# NUCLEO-F410RB-Show.net
KiCad netlist of a schematic drawn in Altium Designer
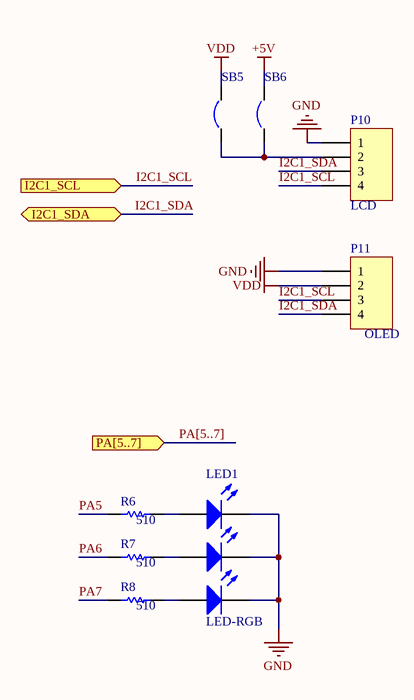
[diagram p0: NUCLEO-F410RB-Show.SchDoc]

(export (version "E")
  (design (tool "Eeschema 10.0.6"))
  (components
    (comp (ref "LED1")
      (value "LED-RGB")
      (footprint "LED-SMD_6PIN-L1.60-W1.50-BL-RD")
      (description "Typical INFRARED GaAs LED")
      (fields (field (name "PUBLISHER") "Altium Limited"))
      (libsource (lib "baselib") (part "LED-RGB"))
    )
    (comp (ref "P10")
      (value "LCD")
      (footprint "HDR1X4")
      (description "Header, 4-Pin")
      (fields (field (name "PUBLISHER") "Altium Limited"))
      (libsource (lib "Connectors") (part "Header 4"))
    )
    (comp (ref "P11")
      (value "OLED")
      (footprint "HDR1X4")
      (description "Header, 4-Pin")
      (fields (field (name "PUBLISHER") "Altium Limited"))
      (libsource (lib "Connectors") (part "Header 4"))
    )
    (comp (ref "R6")
      (value "510")
      (footprint "R0603")
      (description "Resistor")
      (fields (field (name "Comment") "Res_US") (field (name "PUBLISHER") "Altium Limited"))
      (libsource (lib "baselib") (part "Res_US"))
    )
    (comp (ref "R7")
      (value "510")
      (footprint "R0603")
      (description "Resistor")
      (fields (field (name "Comment") "Res_US") (field (name "PUBLISHER") "Altium Limited"))
      (libsource (lib "baselib") (part "Res_US"))
    )
    (comp (ref "R8")
      (value "510")
      (footprint "R0603")
      (description "Resistor")
      (fields (field (name "Comment") "Res_US") (field (name "PUBLISHER") "Altium Limited"))
      (libsource (lib "baselib") (part "Res_US"))
    )
    (comp (ref "SB5")
      (value "Circuit Breaker")
      (footprint "JP2_SMD")
      (fields (field (name "PUBLISHER") "Altium Limited"))
      (libsource (lib "baselib") (part "Circuit Breaker"))
    )
    (comp (ref "SB6")
      (value "Circuit Breaker")
      (footprint "JP2_SMD")
      (fields (field (name "PUBLISHER") "Altium Limited"))
      (libsource (lib "baselib") (part "Circuit Breaker"))
    )
  )
  (nets
    (net (code "1") (name "+5V") (class "Default")
      (node (ref "SB6") (pin "2") (pinfunction "2_2") (pintype "passive"))
    )
    (net (code "2") (name "/I2C1_SCL") (class "Default")
      (node (ref "P10") (pin "4") (pinfunction "4_4") (pintype "passive"))
      (node (ref "P11") (pin "3") (pinfunction "3_3") (pintype "passive"))
    )
    (net (code "3") (name "/I2C1_SDA") (class "Default")
      (node (ref "P10") (pin "3") (pinfunction "3_3") (pintype "passive"))
      (node (ref "P11") (pin "4") (pinfunction "4_4") (pintype "passive"))
    )
    (net (code "4") (name "/PA5") (class "Default")
      (node (ref "R6") (pin "2") (pinfunction "2_2") (pintype "passive"))
    )
    (net (code "5") (name "/PA6") (class "Default")
      (node (ref "R7") (pin "2") (pinfunction "2_2") (pintype "passive"))
    )
    (net (code "6") (name "/PA7") (class "Default")
      (node (ref "R8") (pin "2") (pinfunction "2_2") (pintype "passive"))
    )
    (net (code "8") (name "GND") (class "Default")
      (node (ref "LED1") (pin "4") (pinfunction "K_4") (pintype "passive"))
      (node (ref "LED1") (pin "5") (pinfunction "K_5") (pintype "passive"))
      (node (ref "LED1") (pin "6") (pinfunction "K_6") (pintype "passive"))
      (node (ref "P10") (pin "1") (pinfunction "1_1") (pintype "passive"))
      (node (ref "P11") (pin "1") (pinfunction "1_1") (pintype "passive"))
    )
    (net (code "9") (name "Net-(LED1-A-Pad1)") (class "Default")
      (node (ref "LED1") (pin "1") (pinfunction "A_1") (pintype "passive"))
      (node (ref "R6") (pin "1") (pinfunction "1_1") (pintype "passive"))
    )
    (net (code "10") (name "Net-(LED1-A-Pad2)") (class "Default")
      (node (ref "LED1") (pin "2") (pinfunction "A_2") (pintype "passive"))
      (node (ref "R7") (pin "1") (pinfunction "1_1") (pintype "passive"))
    )
    (net (code "11") (name "Net-(LED1-A-Pad3)") (class "Default")
      (node (ref "LED1") (pin "3") (pinfunction "A_3") (pintype "passive"))
      (node (ref "R8") (pin "1") (pinfunction "1_1") (pintype "passive"))
    )
    (net (code "12") (name "Net-(P10-Pad2)") (class "Default")
      (node (ref "P10") (pin "2") (pinfunction "2_2") (pintype "passive"))
      (node (ref "SB5") (pin "1") (pinfunction "1_1") (pintype "passive"))
      (node (ref "SB6") (pin "1") (pinfunction "1_1") (pintype "passive"))
    )
    (net (code "13") (name "VDD") (class "Default")
      (node (ref "P11") (pin "2") (pinfunction "2_2") (pintype "passive"))
      (node (ref "SB5") (pin "2") (pinfunction "2_2") (pintype "passive"))
    )
  )
)
